# 3V-16V_-3_3V_Regulator.net
KiCad netlist of a schematic drawn in Altium Designer
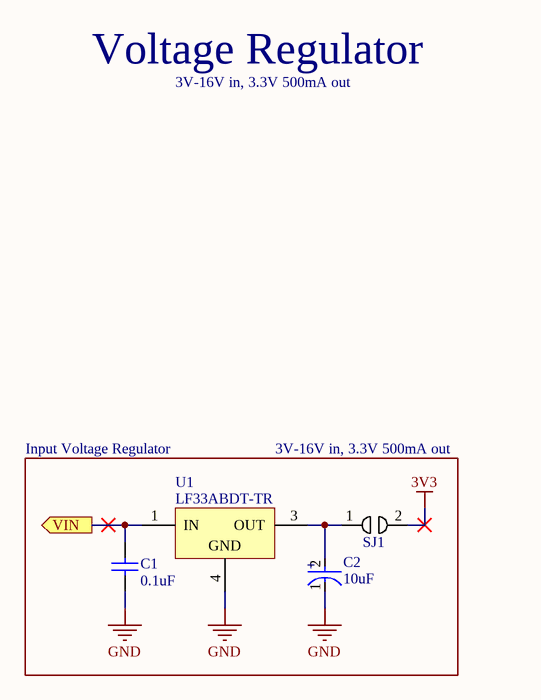
[diagram p0: (3V-16V)-3.3V Regulator.SchDoc]

(export (version "E")
  (design (tool "Eeschema 10.0.6"))
  (components
    (comp (ref "C1")
      (value "0.1uF")
      (footprint "CAPC2013X95X45ML10T25")
      (description "Chip Capacitor, 0.1 uF, +/- 10%, 50 V, 0805 (2012 Metric), RoHS, Tape and Reel")
      (fields
        (field (name "MANUFACTURER") "Samsung Electro-Mechanics")
        (field (name "MANUFACTURER PART NUMBER") "CL21B104KBCNNNC")
      )
      (libsource (lib "Altium Content Vault") (part "CAP-NP-2"))
    )
    (comp (ref "C2")
      (value "10uF")
      (footprint "FP-T491C-MFG")
      (description "CAP TANT 10UF 10% 25V 2312")
      (fields (field (name "TOLERANCE") "10%") (field (name "MANUFACTURER PART NUMBER") "T491C106K025AT"))
      (libsource (lib "Altium Content Vault") (part "203bc49f2ac43e59fd269a8c329ed05"))
    )
    (comp (ref "SJ1")
      (value "Jumper")
      (footprint "35MIL CIRCULAR")
      (description "Solder Jumper to connect or disconnect a trace.")
      (libsource (lib "Solder Jumpers") (part "Jumper"))
    )
    (comp (ref "U1")
      (value "LF33ABDT-TR")
      (footprint "TO-252_N")
      (description "500mA, Very Low Drop (0.45V) Voltage Regulator, 3.3V, 3-Pin DPAK, Tape and Reel")
      (fields (field (name "MANUFACTURER") "STMicroelectronics") (field (name "VOLTAGE") "3.3V"))
      (libsource (lib "Altium Content Vault") (part "PM-REG-L4940-SOT3"))
    )
  )
  (nets
    (net (code "1") (name "/VIN") (class "Default")
      (node (ref "C1") (pin "1") (pinfunction "1_1") (pintype "passive"))
      (node (ref "U1") (pin "1") (pinfunction "IN_1") (pintype "power_in"))
    )
    (net (code "2") (name "3V3") (class "Default") (node (ref "SJ1") (pin "2") (pintype "passive")))
    (net (code "3") (name "GND") (class "Default")
      (node (ref "C1") (pin "2") (pinfunction "2_2") (pintype "passive"))
      (node (ref "C2") (pin "1") (pinfunction "C_1") (pintype "passive"))
      (node (ref "U1") (pin "4") (pinfunction "GND_4") (pintype "power_in"))
    )
    (net (code "4") (name "Net-(C2-A)") (class "Default")
      (node (ref "C2") (pin "2") (pinfunction "A_2") (pintype "passive"))
      (node (ref "SJ1") (pin "1") (pintype "passive"))
      (node (ref "U1") (pin "3") (pinfunction "OUT_3") (pintype "power_in"))
    )
  )
)
